# SCH_HUB-CLASE_2025-02-13.net
KiCad netlist of a schematic drawn in EasyEDA
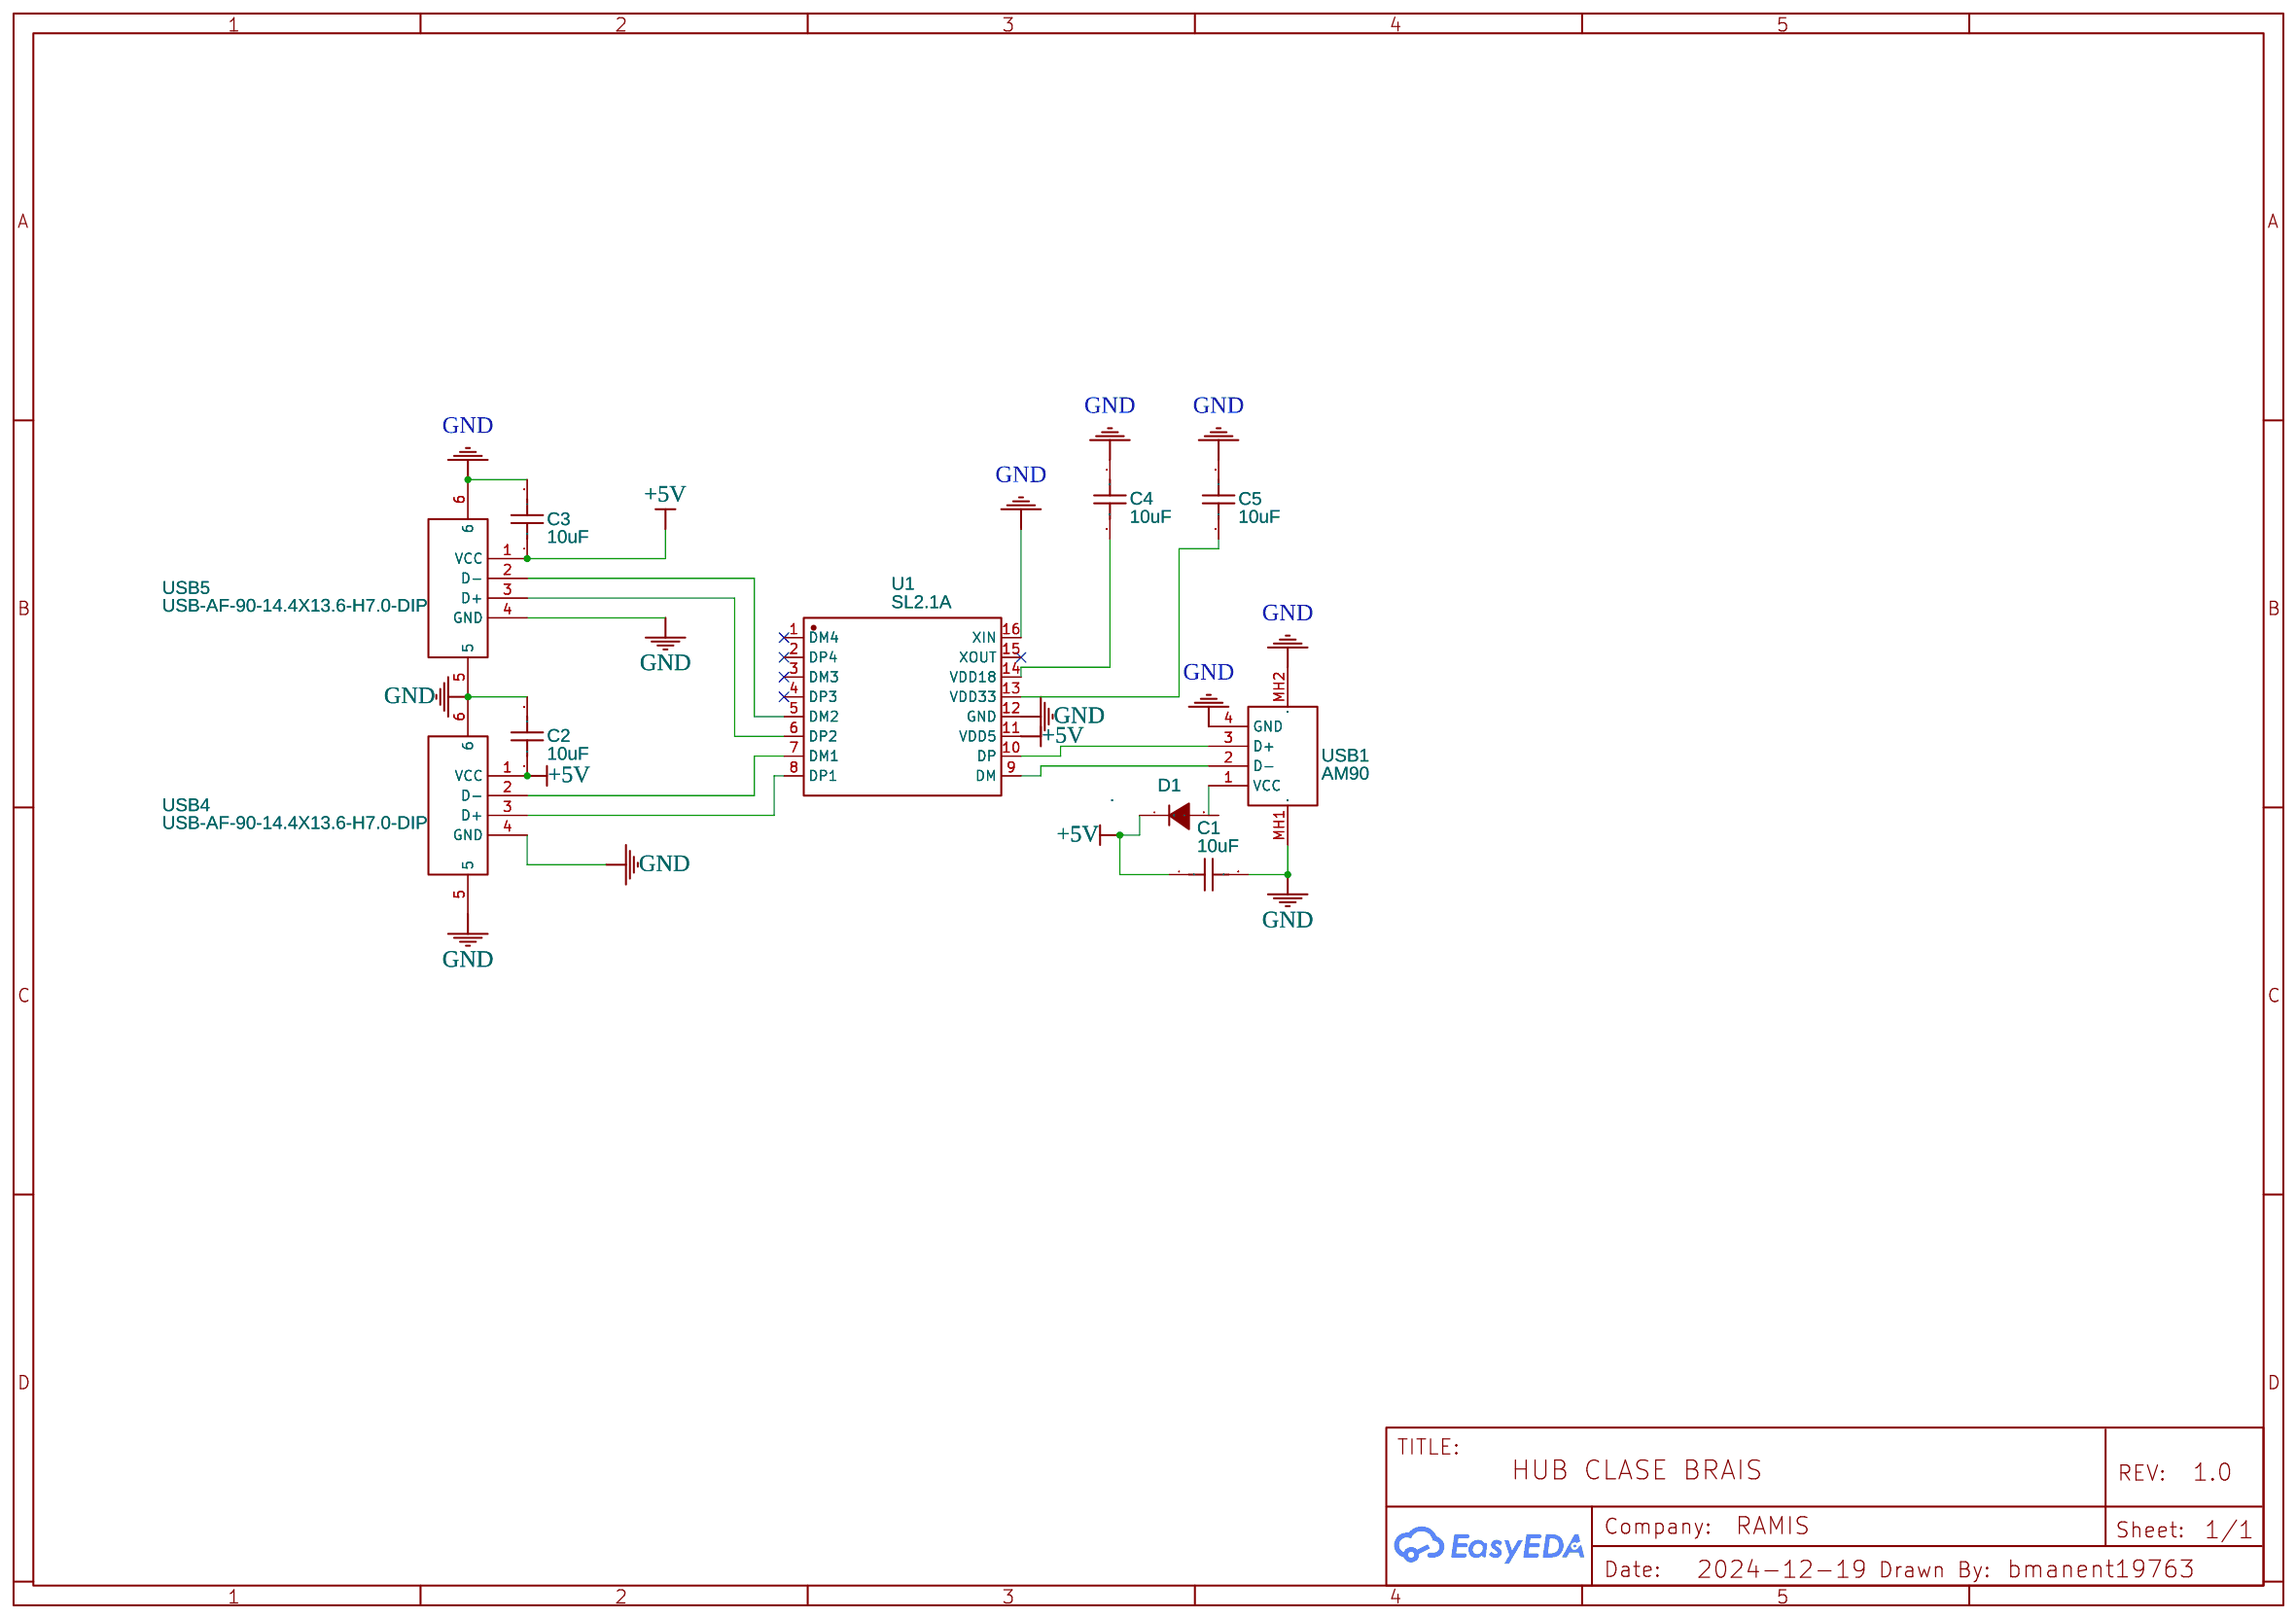
[diagram p0: schematic sheet]

(export (version "E")
  (design (tool "Eeschema 10.0.6"))
  (components
    (comp (ref "C1") (value "10uF") (libsource (lib "") (part "C_0603_US_1")))
    (comp (ref "C2") (value "10uF") (libsource (lib "") (part "C_0603_US")))
    (comp (ref "C3") (value "10uF") (libsource (lib "") (part "C_0603_US")))
    (comp (ref "C4") (value "10uF") (libsource (lib "") (part "C_0603_US_2")))
    (comp (ref "C5") (value "10uF") (libsource (lib "") (part "C_0603_US")))
    (comp (ref "D1")
      (value ".")
      (fields (field (name "Manufacturer Part") "NSR0320MW2T1G") (field (name "Manufacturer") "onsemi(安森美)"))
      (libsource (lib "") (part "NSR0320MW2T1G"))
    )
    (comp (ref "U1")
      (value "SL2.1A")
      (fields (field (name "Manufacturer") "CoreChips(和芯润德)"))
      (libsource (lib "") (part "SL2.1A"))
    )
    (comp (ref "USB1")
      (value "AM90")
      (fields (field (name "Manufacturer") "SHOU HAN(首韩)"))
      (libsource (lib "") (part "AM90"))
    )
    (comp (ref "USB4")
      (value "USB-AF-90-14.4X13.6-H7.0-DIP")
      (fields (field (name "Manufacturer Part") "903-131A1011D10100") (field (name "Manufacturer") "精拓金"))
      (libsource (lib "") (part "USB-AF-90-14.4X13.6-H7.0-DIP"))
    )
    (comp (ref "USB5")
      (value "USB-AF-90-14.4X13.6-H7.0-DIP")
      (fields (field (name "Manufacturer Part") "903-131A1011D10100") (field (name "Manufacturer") "精拓金"))
      (libsource (lib "") (part "USB-AF-90-14.4X13.6-H7.0-DIP"))
    )
  )
  (nets
    (net (code "1") (name "+5V") (class "Default")
      (node (ref "C1") (pin "1") (pinfunction "1_1") (pintype "unspecified"))
      (node (ref "C2") (pin "1") (pinfunction "1_1") (pintype "unspecified"))
      (node (ref "C3") (pin "1") (pinfunction "1_1") (pintype "unspecified"))
      (node (ref "D1") (pin "1") (pinfunction "C_1") (pintype "unspecified"))
      (node (ref "U1") (pin "11") (pinfunction "VDD5_11") (pintype "unspecified"))
      (node (ref "USB4") (pin "1") (pinfunction "VCC_1") (pintype "unspecified"))
      (node (ref "USB5") (pin "1") (pinfunction "VCC_1") (pintype "unspecified"))
    )
    (net (code "2") (name "GND") (class "Default")
      (node (ref "C1") (pin "2") (pinfunction "2_2") (pintype "unspecified"))
      (node (ref "C2") (pin "2") (pinfunction "2_2") (pintype "unspecified"))
      (node (ref "C3") (pin "2") (pinfunction "2_2") (pintype "unspecified"))
      (node (ref "C4") (pin "1") (pinfunction "1_1") (pintype "unspecified"))
      (node (ref "C5") (pin "2") (pinfunction "2_2") (pintype "unspecified"))
      (node (ref "U1") (pin "12") (pinfunction "GND_12") (pintype "unspecified"))
      (node (ref "U1") (pin "16") (pinfunction "XIN_16") (pintype "unspecified"))
      (node (ref "USB1") (pin "4") (pinfunction "GND_4") (pintype "input"))
      (node (ref "USB1") (pin "MH1") (pinfunction "MH1_MH1") (pintype "unspecified"))
      (node (ref "USB1") (pin "MH2") (pinfunction "MH2_MH2") (pintype "unspecified"))
      (node (ref "USB4") (pin "4") (pinfunction "GND_4") (pintype "unspecified"))
      (node (ref "USB4") (pin "5") (pinfunction "5_5") (pintype "unspecified"))
      (node (ref "USB4") (pin "6") (pinfunction "6_6") (pintype "unspecified"))
      (node (ref "USB5") (pin "4") (pinfunction "GND_4") (pintype "unspecified"))
      (node (ref "USB5") (pin "5") (pinfunction "5_5") (pintype "unspecified"))
      (node (ref "USB5") (pin "6") (pinfunction "6_6") (pintype "unspecified"))
    )
    (net (code "3") (name "Net-(D1-A)") (class "Default")
      (node (ref "D1") (pin "2") (pinfunction "A_2") (pintype "unspecified"))
      (node (ref "USB1") (pin "1") (pinfunction "VCC_1") (pintype "input"))
    )
    (net (code "4") (name "Net-(U1-DM)") (class "Default")
      (node (ref "U1") (pin "9") (pinfunction "DM_9") (pintype "unspecified"))
      (node (ref "USB1") (pin "2") (pinfunction "D-_2") (pintype "input"))
    )
    (net (code "5") (name "Net-(U1-DM1)") (class "Default")
      (node (ref "U1") (pin "7") (pinfunction "DM1_7") (pintype "unspecified"))
      (node (ref "USB4") (pin "2") (pinfunction "D-_2") (pintype "unspecified"))
    )
    (net (code "6") (name "Net-(U1-DM2)") (class "Default")
      (node (ref "U1") (pin "5") (pinfunction "DM2_5") (pintype "unspecified"))
      (node (ref "USB5") (pin "2") (pinfunction "D-_2") (pintype "unspecified"))
    )
    (net (code "7") (name "Net-(U1-DP)") (class "Default")
      (node (ref "U1") (pin "10") (pinfunction "DP_10") (pintype "unspecified"))
      (node (ref "USB1") (pin "3") (pinfunction "D+_3") (pintype "input"))
    )
    (net (code "8") (name "Net-(U1-DP1)") (class "Default")
      (node (ref "U1") (pin "8") (pinfunction "DP1_8") (pintype "unspecified"))
      (node (ref "USB4") (pin "3") (pinfunction "D+_3") (pintype "unspecified"))
    )
    (net (code "9") (name "Net-(U1-DP2)") (class "Default")
      (node (ref "U1") (pin "6") (pinfunction "DP2_6") (pintype "unspecified"))
      (node (ref "USB5") (pin "3") (pinfunction "D+_3") (pintype "unspecified"))
    )
    (net (code "10") (name "Net-(U1-VDD18)") (class "Default")
      (node (ref "C4") (pin "2") (pinfunction "2_2") (pintype "unspecified"))
      (node (ref "U1") (pin "14") (pinfunction "VDD18_14") (pintype "unspecified"))
    )
    (net (code "11") (name "Net-(U1-VDD33)") (class "Default")
      (node (ref "C5") (pin "1") (pinfunction "1_1") (pintype "unspecified"))
      (node (ref "U1") (pin "13") (pinfunction "VDD33_13") (pintype "unspecified"))
    )
    (net (code "12") (name "unconnected-(U1-DM3-Pad3)") (class "Default")
      (node (ref "U1") (pin "3") (pinfunction "DM3_3") (pintype "unspecified+no_connect"))
    )
    (net (code "13") (name "unconnected-(U1-DM4-Pad1)") (class "Default")
      (node (ref "U1") (pin "1") (pinfunction "DM4_1") (pintype "unspecified+no_connect"))
    )
    (net (code "14") (name "unconnected-(U1-DP3-Pad4)") (class "Default")
      (node (ref "U1") (pin "4") (pinfunction "DP3_4") (pintype "unspecified+no_connect"))
    )
    (net (code "15") (name "unconnected-(U1-DP4-Pad2)") (class "Default")
      (node (ref "U1") (pin "2") (pinfunction "DP4_2") (pintype "unspecified+no_connect"))
    )
    (net (code "16") (name "unconnected-(U1-XOUT-Pad15)") (class "Default")
      (node (ref "U1") (pin "15") (pinfunction "XOUT_15") (pintype "unspecified+no_connect"))
    )
  )
)
